# Slave_V1.net
KiCad netlist of a schematic drawn in Altium Designer
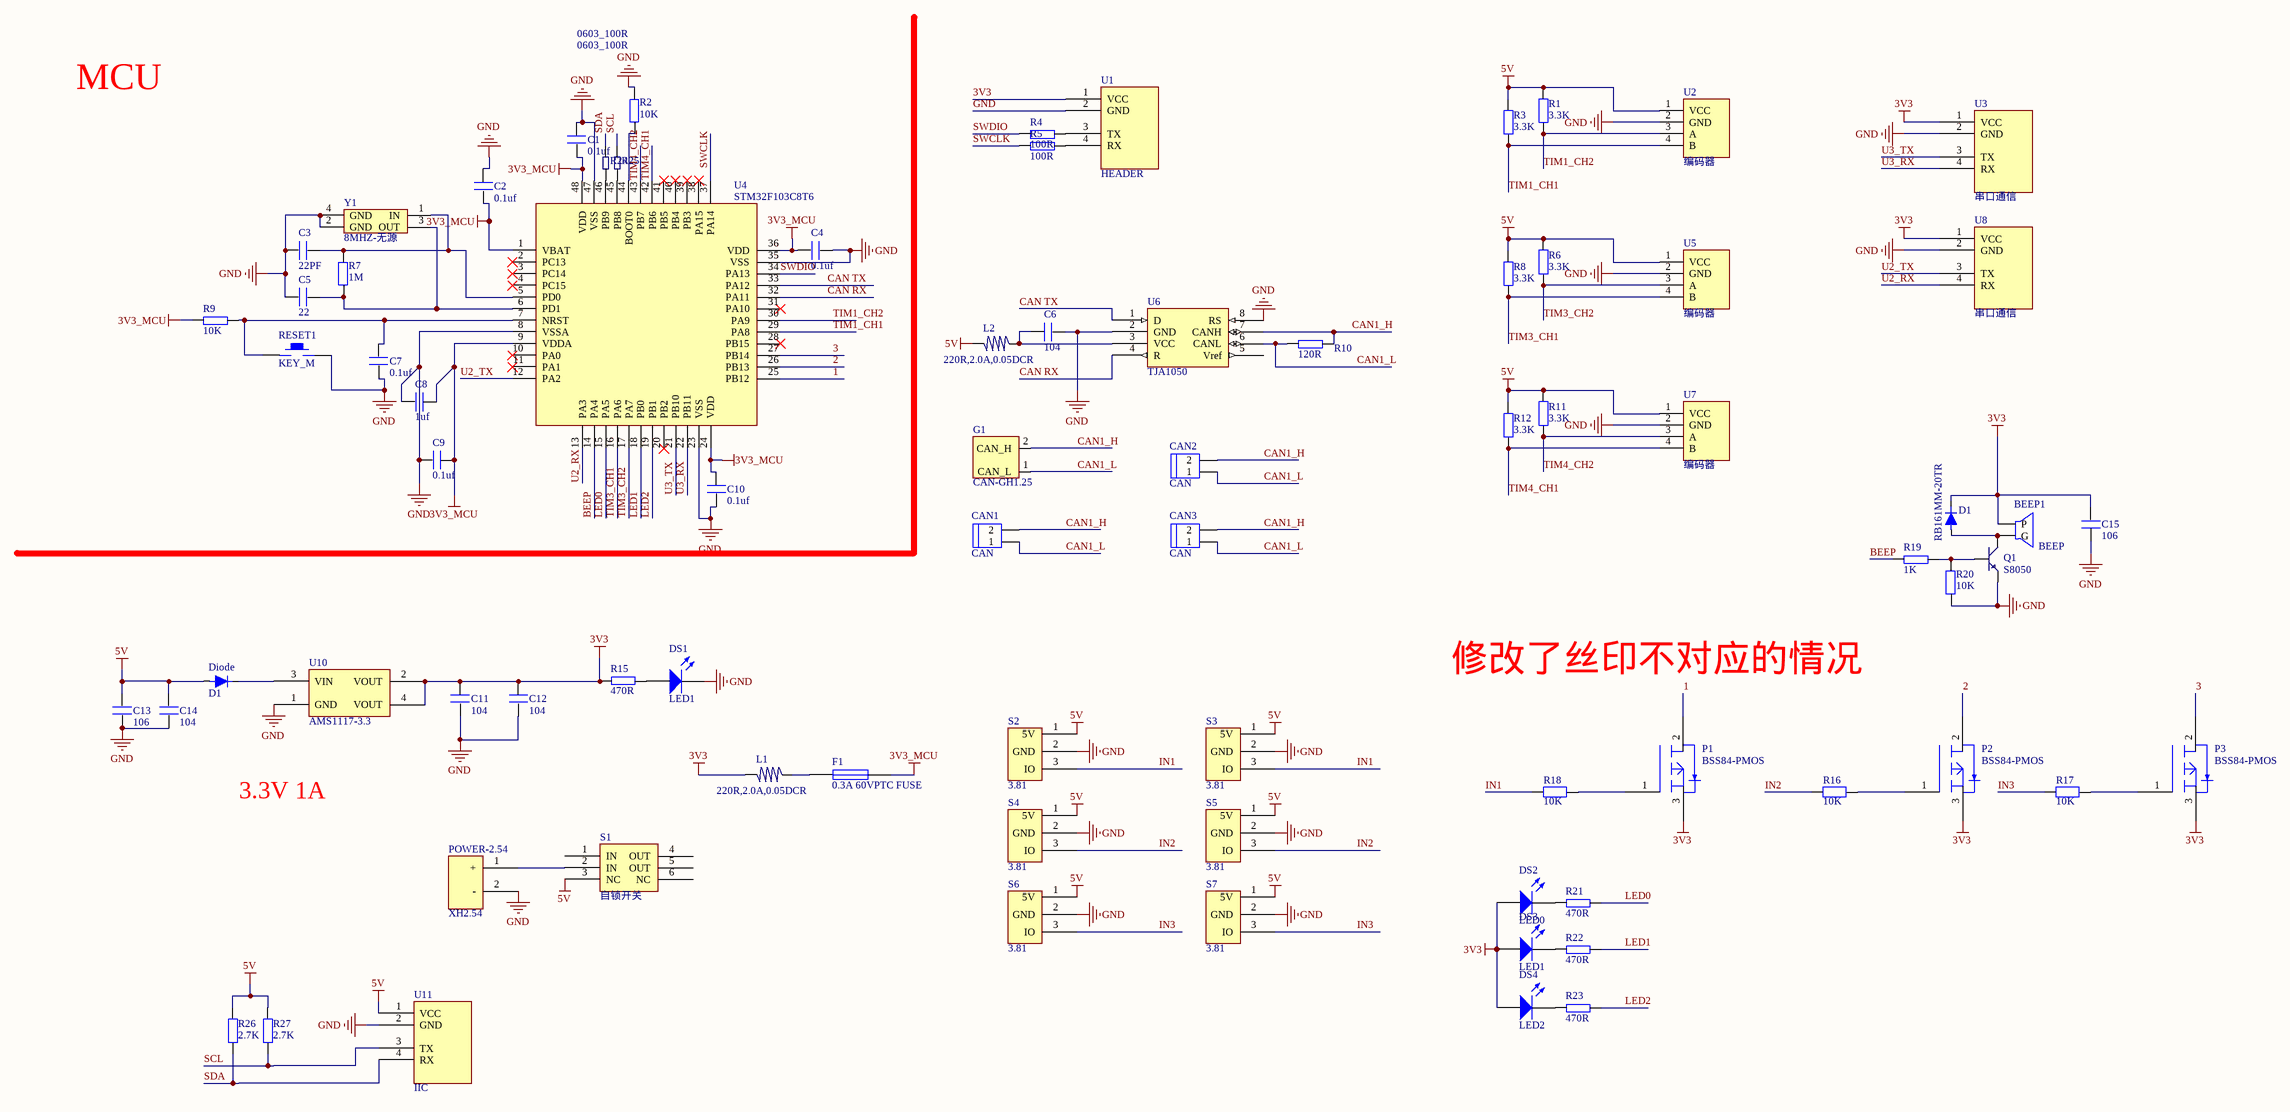
[diagram p0: Slave_V1.SchDoc]

(export (version "E")
  (design (tool "Eeschema 10.0.6"))
  (components
    (comp (ref "BEEP1")
      (value "BEEP")
      (footprint "BELL-5")
      (libsource (lib "Explorer STM32F407封装库") (part "BEEP"))
    )
    (comp (ref "C1") (value "0.1uf") (footprint "0603P") (libsource (lib "Explorer STM32F407封装库") (part "C")))
    (comp (ref "C2") (value "0.1uf") (footprint "0603P") (libsource (lib "Explorer STM32F407封装库") (part "C")))
    (comp (ref "C3") (value "22PF") (footprint "0603P") (libsource (lib "Explorer STM32F407封装库") (part "C")))
    (comp (ref "C4") (value "0.1uf") (footprint "0603P") (libsource (lib "Explorer STM32F407封装库") (part "C")))
    (comp (ref "C5") (value "22") (footprint "0603P") (libsource (lib "Explorer STM32F407封装库") (part "C")))
    (comp (ref "C6") (value "104") (footprint "0603P") (libsource (lib "Explorer STM32F407封装库") (part "C")))
    (comp (ref "C7") (value "0.1uf") (footprint "0603P") (libsource (lib "Explorer STM32F407封装库") (part "C")))
    (comp (ref "C8") (value "1uf") (footprint "0603P") (libsource (lib "Explorer STM32F407封装库") (part "C")))
    (comp (ref "C9") (value "0.1uf") (footprint "0603P") (libsource (lib "Explorer STM32F407封装库") (part "C")))
    (comp (ref "C10")
      (value "0.1uf")
      (footprint "0603P")
      (libsource (lib "Explorer STM32F407封装库") (part "C"))
    )
    (comp (ref "C11")
      (value "104")
      (footprint "0603P")
      (libsource (lib "Explorer STM32F407封装库_SCH") (part "C"))
    )
    (comp (ref "C12")
      (value "104")
      (footprint "0603P")
      (libsource (lib "Explorer STM32F407封装库_SCH") (part "C"))
    )
    (comp (ref "C13")
      (value "106")
      (footprint "0603P")
      (libsource (lib "Explorer STM32F407封装库_SCH") (part "C"))
    )
    (comp (ref "C14")
      (value "104")
      (footprint "0603P")
      (libsource (lib "Explorer STM32F407封装库_SCH") (part "C"))
    )
    (comp (ref "C15") (value "106") (footprint "0603C") (libsource (lib "Explorer STM32F407封装库") (part "C")))
    (comp (ref "CAN1")
      (value "CAN")
      (footprint "HEAD2L-0.8")
      (libsource (lib "Explorer STM32F407封装库") (part "HEAD2"))
    )
    (comp (ref "CAN2")
      (value "CAN")
      (footprint "XH2.54-2")
      (libsource (lib "Explorer STM32F407封装库") (part "HEAD2"))
    )
    (comp (ref "CAN3")
      (value "CAN")
      (footprint "XH2.54-2")
      (libsource (lib "Explorer STM32F407封装库") (part "HEAD2"))
    )
    (comp (ref "D1")
      (value "RB161MM-20TR")
      (footprint "LC-SOD-123F")
      (libsource (lib "主控V2.0弱电") (part "肖特基"))
    )
    (comp (ref "Diode") (value "D1") (footprint "LC-SOD-123F") (libsource (lib "SCHlib") (part "肖特基")))
    (comp (ref "DS1")
      (value "LED1")
      (footprint "0603_LED")
      (description "Typical RED, GREEN, YELLOW, AMBER GaAs LED")
      (fields (field (name "PUBLISHER") "Altium Limited"))
      (libsource (lib "Explorer STM32F407封装库") (part "LED2"))
    )
    (comp (ref "DS2")
      (value "LED0")
      (footprint "0603_LED")
      (description "Typical RED, GREEN, YELLOW, AMBER GaAs LED")
      (fields (field (name "PUBLISHER") "Altium Limited"))
      (libsource (lib "Explorer STM32F407封装库") (part "LED2"))
    )
    (comp (ref "DS3")
      (value "LED1")
      (footprint "0603_LED")
      (description "Typical RED, GREEN, YELLOW, AMBER GaAs LED")
      (fields (field (name "PUBLISHER") "Altium Limited"))
      (libsource (lib "Explorer STM32F407封装库") (part "LED2"))
    )
    (comp (ref "DS4")
      (value "LED2")
      (footprint "0603_LED")
      (description "Typical RED, GREEN, YELLOW, AMBER GaAs LED")
      (fields (field (name "PUBLISHER") "Altium Limited"))
      (libsource (lib "Explorer STM32F407封装库") (part "LED2"))
    )
    (comp (ref "F1")
      (value "0.3A 60VPTC FUSE")
      (footprint "LC-1812_R")
      (description "Fuse")
      (fields (field (name "PUBLISHER") "Altium Limited"))
      (libsource (lib "羽毛球团队") (part "Fuse 1_2"))
    )
    (comp (ref "G1")
      (value "CAN-GH1.25")
      (footprint "GH1.25_1*2_lishi")
      (libsource (lib "SCHlib") (part "GH1.25-CAN"))
    )
    (comp (ref "L1")
      (value "220R,2.0A,0.05DCR")
      (footprint "L_0603")
      (libsource (lib "Explorer STM32F407封装库") (part "L"))
    )
    (comp (ref "L2")
      (value "220R,2.0A,0.05DCR")
      (footprint "0603P")
      (libsource (lib "Explorer STM32F407封装库") (part "L"))
    )
    (comp (ref "P1")
      (value "BSS84-PMOS")
      (footprint "LC-SOT-23(SOT-23-3)")
      (libsource (lib "SCHlib") (part "BSS84-PMOS"))
    )
    (comp (ref "P2")
      (value "BSS84-PMOS")
      (footprint "LC-SOT-23(SOT-23-3)")
      (libsource (lib "SCHlib") (part "BSS84-PMOS"))
    )
    (comp (ref "P3")
      (value "BSS84-PMOS")
      (footprint "LC-SOT-23(SOT-23-3)")
      (libsource (lib "SCHlib") (part "BSS84-PMOS"))
    )
    (comp (ref "POWER-2.54")
      (value "XH2.54")
      (footprint "XH2.54-2")
      (libsource (lib "SCHlib") (part "XH2.54-2"))
    )
    (comp (ref "Q1")
      (value "S8050")
      (footprint "SOT-23R")
      (description "8050/BCW846/BCW847")
      (libsource (lib "Explorer STM32F407封装库") (part "NPN"))
    )
    (comp (ref "R1")
      (value "3.3K")
      (footprint "0603P")
      (description "R-0805")
      (libsource (lib "羽毛球团队") (part "R-0805"))
    )
    (comp (ref "R2") (value "10K") (footprint "0603P") (libsource (lib "Explorer STM32F407封装库") (part "R")))
    (comp (ref "R3")
      (value "3.3K")
      (footprint "0603P")
      (description "R-0805")
      (libsource (lib "羽毛球团队") (part "R-0805"))
    )
    (comp (ref "R4") (value "100R") (footprint "0603P") (libsource (lib "Explorer STM32F407封装库") (part "R")))
    (comp (ref "R5") (value "100R") (footprint "0603P") (libsource (lib "Explorer STM32F407封装库") (part "R")))
    (comp (ref "R6")
      (value "3.3K")
      (footprint "0603P")
      (description "R-0805")
      (libsource (lib "羽毛球团队") (part "R-0805"))
    )
    (comp (ref "R7") (value "1M") (footprint "0603P") (libsource (lib "Explorer STM32F407封装库") (part "R")))
    (comp (ref "R8")
      (value "3.3K")
      (footprint "0603P")
      (description "R-0805")
      (libsource (lib "羽毛球团队") (part "R-0805"))
    )
    (comp (ref "R9") (value "10K") (footprint "0603P") (libsource (lib "Explorer STM32F407封装库") (part "R")))
    (comp (ref "R10") (value "120R") (footprint "0603P") (libsource (lib "Explorer STM32F407封装库") (part "R")))
    (comp (ref "R11")
      (value "3.3K")
      (footprint "0603P")
      (description "R-0805")
      (libsource (lib "羽毛球团队") (part "R-0805"))
    )
    (comp (ref "R12")
      (value "3.3K")
      (footprint "0603P")
      (description "R-0805")
      (libsource (lib "羽毛球团队") (part "R-0805"))
    )
    (comp (ref "R15")
      (value "470R")
      (footprint "0603P")
      (libsource (lib "Explorer STM32F407封装库_SCH") (part "R"))
    )
    (comp (ref "R16")
      (value "10K")
      (footprint "0603P")
      (description "R-0805")
      (libsource (lib "") (part "R-0805_1"))
    )
    (comp (ref "R17")
      (value "10K")
      (footprint "0603P")
      (description "R-0805")
      (libsource (lib "") (part "R-0805_1"))
    )
    (comp (ref "R18")
      (value "10K")
      (footprint "0603P")
      (description "R-0805")
      (libsource (lib "") (part "R-0805_1"))
    )
    (comp (ref "R19") (value "1K") (footprint "0603R") (libsource (lib "Explorer STM32F407封装库") (part "R")))
    (comp (ref "R20") (value "10K") (footprint "0603R") (libsource (lib "Explorer STM32F407封装库") (part "R")))
    (comp (ref "R21") (value "470R") (footprint "0603R") (libsource (lib "Explorer STM32F407封装库") (part "R")))
    (comp (ref "R22") (value "470R") (footprint "0603R") (libsource (lib "Explorer STM32F407封装库") (part "R")))
    (comp (ref "R23") (value "470R") (footprint "0603R") (libsource (lib "Explorer STM32F407封装库") (part "R")))
    (comp (ref "R24") (value "0603_100R") (footprint "0603R") (libsource (lib "Schlib1") (part "RES")))
    (comp (ref "R25") (value "0603_100R") (footprint "0603R") (libsource (lib "Schlib1") (part "RES")))
    (comp (ref "R26")
      (value "2.7K")
      (footprint "0603R")
      (description "R-0805")
      (libsource (lib "") (part "R-0805_2"))
    )
    (comp (ref "R27")
      (value "2.7K")
      (footprint "0603R")
      (description "R-0805")
      (libsource (lib "") (part "R-0805_2"))
    )
    (comp (ref "RESET1")
      (value "KEY_M")
      (footprint "KEY_M")
      (libsource (lib "Explorer STM32F407封装库_SCH") (part "KEY_M"))
    )
    (comp (ref "S1") (value "自锁开关") (footprint "自锁开关5.8*5.8") (libsource (lib "SCHlib") (part "Switch_5.8")))
    (comp (ref "S2") (value "3.81") (footprint "KF2EDG-3.81-3P-弯针") (libsource (lib "SCHlib") (part "槽型开关")))
    (comp (ref "S3") (value "3.81") (footprint "KF2EDG-3.81-3P-弯针") (libsource (lib "SCHlib") (part "槽型开关")))
    (comp (ref "S4") (value "3.81") (footprint "KF2EDG-3.81-3P-弯针") (libsource (lib "SCHlib") (part "槽型开关")))
    (comp (ref "S5") (value "3.81") (footprint "KF2EDG-3.81-3P-弯针") (libsource (lib "SCHlib") (part "槽型开关")))
    (comp (ref "S6") (value "3.81") (footprint "KF2EDG-3.81-3P-弯针") (libsource (lib "SCHlib") (part "槽型开关")))
    (comp (ref "S7") (value "3.81") (footprint "KF2EDG-3.81-3P-弯针") (libsource (lib "SCHlib") (part "槽型开关")))
    (comp (ref "U1") (value "HEADER") (footprint "XH2.54-4") (libsource (lib "羽毛球团队") (part "XH2.54插座-4P")))
    (comp (ref "U2") (value "编码器") (footprint "XH2.54-4") (libsource (lib "SCHlib") (part "编码器4P")))
    (comp (ref "U3") (value "串口通信") (footprint "XH2.54-4") (libsource (lib "羽毛球团队") (part "XH2.54插座-4P")))
    (comp (ref "U4")
      (value "STM32F103C8T6")
      (footprint "LQFP-48_7x7x05P")
      (libsource (lib "RoboFly") (part "STM32F103C8T6"))
    )
    (comp (ref "U5") (value "编码器") (footprint "XH2.54-4") (libsource (lib "SCHlib") (part "编码器4P")))
    (comp (ref "U6")
      (value "TJA1050")
      (footprint "SOP8")
      (libsource (lib "Explorer STM32F407封装库") (part "SN65HVD230D"))
    )
    (comp (ref "U7") (value "编码器") (footprint "XH2.54-4") (libsource (lib "SCHlib") (part "编码器4P")))
    (comp (ref "U8") (value "串口通信") (footprint "XH2.54-4") (libsource (lib "羽毛球团队") (part "XH2.54插座-4P")))
    (comp (ref "U10") (value "AMS1117-3.3") (footprint "SOT223") (libsource (lib "74hc595") (part "AMS1117")))
    (comp (ref "U11") (value "IIC") (footprint "XH2.54-4") (libsource (lib "羽毛球团队") (part "XH2.54插座-4P")))
    (comp (ref "Y1")
      (value "8MHZ-无源")
      (footprint "XTAL3225   无源")
      (libsource (lib "SCHlib") (part "XTAL-3225"))
    )
  )
  (nets
    (net (code "1") (name "/1") (class "Default")
      (node (ref "P1") (pin "2") (pinfunction "D_2") (pintype "passive"))
      (node (ref "U4") (pin "25") (pinfunction "PB12_25") (pintype "passive"))
    )
    (net (code "2") (name "/2") (class "Default")
      (node (ref "P2") (pin "2") (pinfunction "D_2") (pintype "passive"))
      (node (ref "U4") (pin "26") (pinfunction "PB13_26") (pintype "passive"))
    )
    (net (code "3") (name "/3") (class "Default")
      (node (ref "P3") (pin "2") (pinfunction "D_2") (pintype "passive"))
      (node (ref "U4") (pin "27") (pinfunction "PB14_27") (pintype "passive"))
    )
    (net (code "4") (name "/BEEP") (class "Default")
      (node (ref "R19") (pin "1") (pintype "passive"))
      (node (ref "U4") (pin "14") (pinfunction "PA4_14") (pintype "passive"))
    )
    (net (code "5") (name "/CAN RX") (class "Default")
      (node (ref "U4") (pin "32") (pinfunction "PA11_32") (pintype "passive"))
      (node (ref "U6") (pin "4") (pinfunction "R_4") (pintype "output"))
    )
    (net (code "6") (name "/CAN TX") (class "Default")
      (node (ref "U4") (pin "33") (pinfunction "PA12_33") (pintype "passive"))
      (node (ref "U6") (pin "1") (pinfunction "D_1") (pintype "input"))
    )
    (net (code "7") (name "/CAN1_H") (class "Default")
      (node (ref "CAN1") (pin "2") (pinfunction "2_2") (pintype "passive"))
      (node (ref "CAN2") (pin "2") (pinfunction "2_2") (pintype "passive"))
      (node (ref "CAN3") (pin "2") (pinfunction "2_2") (pintype "passive"))
      (node (ref "G1") (pin "2") (pinfunction "CAN_H_2") (pintype "passive"))
      (node (ref "R10") (pin "2") (pintype "passive"))
      (node (ref "U6") (pin "7") (pinfunction "CANH_7") (pintype "bidirectional"))
    )
    (net (code "8") (name "/CAN1_L") (class "Default")
      (node (ref "CAN1") (pin "1") (pinfunction "1_1") (pintype "passive"))
      (node (ref "CAN2") (pin "1") (pinfunction "1_1") (pintype "passive"))
      (node (ref "CAN3") (pin "1") (pinfunction "1_1") (pintype "passive"))
      (node (ref "G1") (pin "1") (pinfunction "CAN_L_1") (pintype "passive"))
      (node (ref "R10") (pin "1") (pintype "passive"))
      (node (ref "U6") (pin "6") (pinfunction "CANL_6") (pintype "bidirectional"))
    )
    (net (code "9") (name "/IN1") (class "Default")
      (node (ref "R18") (pin "1") (pinfunction "1_1") (pintype "passive"))
      (node (ref "S2") (pin "3") (pinfunction "IO_3") (pintype "passive"))
      (node (ref "S3") (pin "3") (pinfunction "IO_3") (pintype "passive"))
    )
    (net (code "10") (name "/IN2") (class "Default")
      (node (ref "R16") (pin "1") (pinfunction "1_1") (pintype "passive"))
      (node (ref "S4") (pin "3") (pinfunction "IO_3") (pintype "passive"))
      (node (ref "S5") (pin "3") (pinfunction "IO_3") (pintype "passive"))
    )
    (net (code "11") (name "/IN3") (class "Default")
      (node (ref "R17") (pin "1") (pinfunction "1_1") (pintype "passive"))
      (node (ref "S6") (pin "3") (pinfunction "IO_3") (pintype "passive"))
      (node (ref "S7") (pin "3") (pinfunction "IO_3") (pintype "passive"))
    )
    (net (code "12") (name "/LED0") (class "Default")
      (node (ref "R21") (pin "2") (pintype "passive"))
      (node (ref "U4") (pin "15") (pinfunction "PA5_15") (pintype "passive"))
    )
    (net (code "13") (name "/LED1") (class "Default")
      (node (ref "R22") (pin "2") (pintype "passive"))
      (node (ref "U4") (pin "18") (pinfunction "PB0_18") (pintype "passive"))
    )
    (net (code "14") (name "/LED2") (class "Default")
      (node (ref "R23") (pin "2") (pintype "passive"))
      (node (ref "U4") (pin "19") (pinfunction "PB1_19") (pintype "passive"))
    )
    (net (code "15") (name "/SCL") (class "Default")
      (node (ref "R25") (pin "2") (pinfunction "2_2") (pintype "passive"))
      (node (ref "R27") (pin "1") (pinfunction "1_1") (pintype "passive"))
      (node (ref "U11") (pin "3") (pinfunction "TX_3") (pintype "passive"))
    )
    (net (code "16") (name "/SDA") (class "Default")
      (node (ref "R24") (pin "2") (pinfunction "2_2") (pintype "passive"))
      (node (ref "R26") (pin "1") (pinfunction "1_1") (pintype "passive"))
      (node (ref "U11") (pin "4") (pinfunction "RX_4") (pintype "passive"))
    )
    (net (code "17") (name "/SWCLK") (class "Default")
      (node (ref "R5") (pin "1") (pintype "passive"))
      (node (ref "U4") (pin "37") (pinfunction "PA14_37") (pintype "passive"))
    )
    (net (code "18") (name "/SWDIO") (class "Default")
      (node (ref "R4") (pin "1") (pintype "passive"))
      (node (ref "U4") (pin "34") (pinfunction "PA13_34") (pintype "passive"))
    )
    (net (code "19") (name "/TIM1_CH1") (class "Default")
      (node (ref "R3") (pin "2") (pinfunction "2_2") (pintype "passive"))
      (node (ref "U2") (pin "4") (pinfunction "B_4") (pintype "passive"))
      (node (ref "U4") (pin "29") (pinfunction "PA8_29") (pintype "passive"))
    )
    (net (code "20") (name "/TIM1_CH2") (class "Default")
      (node (ref "R1") (pin "2") (pinfunction "2_2") (pintype "passive"))
      (node (ref "U2") (pin "3") (pinfunction "A_3") (pintype "passive"))
      (node (ref "U4") (pin "30") (pinfunction "PA9_30") (pintype "passive"))
    )
    (net (code "21") (name "/TIM3_CH1") (class "Default")
      (node (ref "R8") (pin "2") (pinfunction "2_2") (pintype "passive"))
      (node (ref "U4") (pin "16") (pinfunction "PA6_16") (pintype "passive"))
      (node (ref "U5") (pin "4") (pinfunction "B_4") (pintype "passive"))
    )
    (net (code "22") (name "/TIM3_CH2") (class "Default")
      (node (ref "R6") (pin "2") (pinfunction "2_2") (pintype "passive"))
      (node (ref "U4") (pin "17") (pinfunction "PA7_17") (pintype "passive"))
      (node (ref "U5") (pin "3") (pinfunction "A_3") (pintype "passive"))
    )
    (net (code "23") (name "/TIM4_CH1") (class "Default")
      (node (ref "R12") (pin "2") (pinfunction "2_2") (pintype "passive"))
      (node (ref "U4") (pin "42") (pinfunction "PB6_42") (pintype "passive"))
      (node (ref "U7") (pin "4") (pinfunction "B_4") (pintype "passive"))
    )
    (net (code "24") (name "/TIM4_CH2") (class "Default")
      (node (ref "R11") (pin "2") (pinfunction "2_2") (pintype "passive"))
      (node (ref "U4") (pin "43") (pinfunction "PB7_43") (pintype "passive"))
      (node (ref "U7") (pin "3") (pinfunction "A_3") (pintype "passive"))
    )
    (net (code "25") (name "/U2_RX") (class "Default")
      (node (ref "U4") (pin "13") (pinfunction "PA3_13") (pintype "passive"))
      (node (ref "U8") (pin "4") (pinfunction "RX_4") (pintype "passive"))
    )
    (net (code "26") (name "/U2_TX") (class "Default")
      (node (ref "U4") (pin "12") (pinfunction "PA2_12") (pintype "passive"))
      (node (ref "U8") (pin "3") (pinfunction "TX_3") (pintype "passive"))
    )
    (net (code "27") (name "/U3_RX") (class "Default")
      (node (ref "U3") (pin "4") (pinfunction "RX_4") (pintype "passive"))
      (node (ref "U4") (pin "22") (pinfunction "PB11_22") (pintype "passive"))
    )
    (net (code "28") (name "/U3_TX") (class "Default")
      (node (ref "U3") (pin "3") (pinfunction "TX_3") (pintype "passive"))
      (node (ref "U4") (pin "21") (pinfunction "PB10_21") (pintype "passive"))
    )
    (net (code "29") (name "3V3") (class "Default")
      (node (ref "BEEP1") (pin "1") (pinfunction "P_1") (pintype "passive"))
      (node (ref "C11") (pin "2") (pintype "passive"))
      (node (ref "C12") (pin "2") (pintype "passive"))
      (node (ref "C15") (pin "1") (pintype "passive"))
      (node (ref "D1") (pin "2") (pinfunction "2_2") (pintype "passive"))
      (node (ref "DS2") (pin "1") (pinfunction "A_1") (pintype "passive"))
      (node (ref "DS3") (pin "1") (pinfunction "A_1") (pintype "passive"))
      (node (ref "DS4") (pin "1") (pinfunction "A_1") (pintype "passive"))
      (node (ref "L1") (pin "2") (pintype "passive"))
      (node (ref "P1") (pin "3") (pinfunction "S_3") (pintype "passive"))
      (node (ref "P2") (pin "3") (pinfunction "S_3") (pintype "passive"))
      (node (ref "P3") (pin "3") (pinfunction "S_3") (pintype "passive"))
      (node (ref "R15") (pin "2") (pintype "passive"))
      (node (ref "U1") (pin "1") (pinfunction "VCC_1") (pintype "passive"))
      (node (ref "U10") (pin "2") (pinfunction "VOUT_2") (pintype "passive"))
      (node (ref "U10") (pin "4") (pinfunction "VOUT_4") (pintype "passive"))
      (node (ref "U3") (pin "1") (pinfunction "VCC_1") (pintype "passive"))
      (node (ref "U8") (pin "1") (pinfunction "VCC_1") (pintype "passive"))
    )
    (net (code "30") (name "3V3_MCU") (class "Default")
      (node (ref "C1") (pin "1") (pintype "passive"))
      (node (ref "C10") (pin "2") (pintype "passive"))
      (node (ref "C2") (pin "1") (pintype "passive"))
      (node (ref "C4") (pin "2") (pintype "passive"))
      (node (ref "C8") (pin "1") (pintype "passive"))
      (node (ref "C9") (pin "1") (pintype "passive"))
      (node (ref "F1") (pin "2") (pinfunction "2_2") (pintype "passive"))
      (node (ref "R9") (pin "1") (pintype "passive"))
      (node (ref "U4") (pin "1") (pinfunction "VBAT_1") (pintype "passive"))
      (node (ref "U4") (pin "24") (pinfunction "VDD_24") (pintype "passive"))
      (node (ref "U4") (pin "36") (pinfunction "VDD_36") (pintype "passive"))
      (node (ref "U4") (pin "48") (pinfunction "VDD_48") (pintype "passive"))
      (node (ref "U4") (pin "9") (pinfunction "VDDA_9") (pintype "passive"))
    )
    (net (code "31") (name "5V") (class "Default")
      (node (ref "C13") (pin "2") (pintype "passive"))
      (node (ref "C14") (pin "2") (pintype "passive"))
      (node (ref "Diode") (pin "1") (pinfunction "1_1") (pintype "passive"))
      (node (ref "L2") (pin "2") (pintype "passive"))
      (node (ref "R1") (pin "1") (pinfunction "1_1") (pintype "passive"))
      (node (ref "R11") (pin "1") (pinfunction "1_1") (pintype "passive"))
      (node (ref "R12") (pin "1") (pinfunction "1_1") (pintype "passive"))
      (node (ref "R26") (pin "2") (pinfunction "2_2") (pintype "passive"))
      (node (ref "R27") (pin "2") (pinfunction "2_2") (pintype "passive"))
      (node (ref "R3") (pin "1") (pinfunction "1_1") (pintype "passive"))
      (node (ref "R6") (pin "1") (pinfunction "1_1") (pintype "passive"))
      (node (ref "R8") (pin "1") (pinfunction "1_1") (pintype "passive"))
      (node (ref "S1") (pin "3") (pinfunction "NC_3") (pintype "passive"))
      (node (ref "S2") (pin "1") (pinfunction "5V_1") (pintype "passive"))
      (node (ref "S3") (pin "1") (pinfunction "5V_1") (pintype "passive"))
      (node (ref "S4") (pin "1") (pinfunction "5V_1") (pintype "passive"))
      (node (ref "S5") (pin "1") (pinfunction "5V_1") (pintype "passive"))
      (node (ref "S6") (pin "1") (pinfunction "5V_1") (pintype "passive"))
      (node (ref "S7") (pin "1") (pinfunction "5V_1") (pintype "passive"))
      (node (ref "U11") (pin "1") (pinfunction "VCC_1") (pintype "passive"))
      (node (ref "U2") (pin "1") (pinfunction "VCC_1") (pintype "passive"))
      (node (ref "U5") (pin "1") (pinfunction "VCC_1") (pintype "passive"))
      (node (ref "U7") (pin "1") (pinfunction "VCC_1") (pintype "passive"))
    )
    (net (code "32") (name "GND") (class "Default")
      (node (ref "C1") (pin "2") (pintype "passive"))
      (node (ref "C10") (pin "1") (pintype "passive"))
      (node (ref "C11") (pin "1") (pintype "passive"))
      (node (ref "C12") (pin "1") (pintype "passive"))
      (node (ref "C13") (pin "1") (pintype "passive"))
      (node (ref "C14") (pin "1") (pintype "passive"))
      (node (ref "C15") (pin "2") (pintype "passive"))
      (node (ref "C2") (pin "2") (pintype "passive"))
      (node (ref "C3") (pin "2") (pintype "passive"))
      (node (ref "C4") (pin "1") (pintype "passive"))
      (node (ref "C5") (pin "2") (pintype "passive"))
      (node (ref "C6") (pin "2") (pintype "passive"))
      (node (ref "C7") (pin "1") (pintype "passive"))
      (node (ref "C8") (pin "2") (pintype "passive"))
      (node (ref "C9") (pin "2") (pintype "passive"))
      (node (ref "DS1") (pin "2") (pinfunction "K_2") (pintype "passive"))
      (node (ref "POWER-2.54") (pin "2") (pinfunction "-_2") (pintype "passive"))
      (node (ref "Q1") (pin "1") (pinfunction "E_1") (pintype "passive"))
      (node (ref "R2") (pin "1") (pintype "passive"))
      (node (ref "R20") (pin "2") (pintype "passive"))
      (node (ref "RESET1") (pin "2") (pinfunction "2_2") (pintype "passive"))
      (node (ref "S2") (pin "2") (pinfunction "GND_2") (pintype "passive"))
      (node (ref "S3") (pin "2") (pinfunction "GND_2") (pintype "passive"))
      (node (ref "S4") (pin "2") (pinfunction "GND_2") (pintype "passive"))
      (node (ref "S5") (pin "2") (pinfunction "GND_2") (pintype "passive"))
      (node (ref "S6") (pin "2") (pinfunction "GND_2") (pintype "passive"))
      (node (ref "S7") (pin "2") (pinfunction "GND_2") (pintype "passive"))
      (node (ref "U1") (pin "2") (pinfunction "GND_2") (pintype "passive"))
      (node (ref "U10") (pin "1") (pinfunction "GND_1") (pintype "passive"))
      (node (ref "U11") (pin "2") (pinfunction "GND_2") (pintype "passive"))
      (node (ref "U2") (pin "2") (pinfunction "GND_2") (pintype "passive"))
      (node (ref "U3") (pin "2") (pinfunction "GND_2") (pintype "passive"))
      (node (ref "U4") (pin "23") (pinfunction "VSS_23") (pintype "passive"))
      (node (ref "U4") (pin "35") (pinfunction "VSS_35") (pintype "passive"))
      (node (ref "U4") (pin "47") (pinfunction "VSS_47") (pintype "passive"))
      (node (ref "U4") (pin "8") (pinfunction "VSSA_8") (pintype "passive"))
      (node (ref "U5") (pin "2") (pinfunction "GND_2") (pintype "passive"))
      (node (ref "U6") (pin "2") (pinfunction "GND_2") (pintype "power_in"))
      (node (ref "U6") (pin "8") (pinfunction "RS_8") (pintype "input"))
      (node (ref "U7") (pin "2") (pinfunction "GND_2") (pintype "passive"))
      (node (ref "U8") (pin "2") (pinfunction "GND_2") (pintype "passive"))
      (node (ref "Y1") (pin "2") (pinfunction "GND_2") (pintype "passive"))
      (node (ref "Y1") (pin "4") (pinfunction "GND_4") (pintype "passive"))
    )
    (net (code "33") (name "Net-(BEEP1-G)") (class "Default")
      (node (ref "BEEP1") (pin "2") (pinfunction "G_2") (pintype "passive"))
      (node (ref "D1") (pin "1") (pinfunction "1_1") (pintype "passive"))
      (node (ref "Q1") (pin "3") (pinfunction "C_3") (pintype "passive"))
    )
    (net (code "34") (name "Net-(DS1-A)") (class "Default")
      (node (ref "DS1") (pin "1") (pinfunction "A_1") (pintype "passive"))
      (node (ref "R15") (pin "1") (pintype "passive"))
    )
    (net (code "35") (name "Net-(DS2-K)") (class "Default")
      (node (ref "DS2") (pin "2") (pinfunction "K_2") (pintype "passive"))
      (node (ref "R21") (pin "1") (pintype "passive"))
    )
    (net (code "36") (name "Net-(DS3-K)") (class "Default")
      (node (ref "DS3") (pin "2") (pinfunction "K_2") (pintype "passive"))
      (node (ref "R22") (pin "1") (pintype "passive"))
    )
    (net (code "37") (name "Net-(DS4-K)") (class "Default")
      (node (ref "DS4") (pin "2") (pinfunction "K_2") (pintype "passive"))
      (node (ref "R23") (pin "1") (pintype "passive"))
    )
    (net (code "38") (name "Net-(F1-Pad1)") (class "Default")
      (node (ref "F1") (pin "1") (pinfunction "1_1") (pintype "passive"))
      (node (ref "L1") (pin "1") (pintype "passive"))
    )
    (net (code "39") (name "Net-(P1-G)") (class "Default")
      (node (ref "P1") (pin "1") (pinfunction "G_1") (pintype "passive"))
      (node (ref "R18") (pin "2") (pinfunction "2_2") (pintype "passive"))
    )
    (net (code "40") (name "Net-(P2-G)") (class "Default")
      (node (ref "P2") (pin "1") (pinfunction "G_1") (pintype "passive"))
      (node (ref "R16") (pin "2") (pinfunction "2_2") (pintype "passive"))
    )
    (net (code "41") (name "Net-(P3-G)") (class "Default")
      (node (ref "P3") (pin "1") (pinfunction "G_1") (pintype "passive"))
      (node (ref "R17") (pin "2") (pinfunction "2_2") (pintype "passive"))
    )
    (net (code "42") (name "Net-(POWER-2.54-+)") (class "Default")
      (node (ref "POWER-2.54") (pin "1") (pinfunction "+_1") (pintype "passive"))
      (node (ref "S1") (pin "2") (pinfunction "IN_2") (pintype "passive"))
    )
    (net (code "43") (name "Net-(Q1-B)") (class "Default")
      (node (ref "Q1") (pin "2") (pinfunction "B_2") (pintype "passive"))
      (node (ref "R19") (pin "2") (pintype "passive"))
      (node (ref "R20") (pin "1") (pintype "passive"))
    )
    (net (code "44") (name "Net-(U1-RX)") (class "Default")
      (node (ref "R5") (pin "2") (pintype "passive"))
      (node (ref "U1") (pin "4") (pinfunction "RX_4") (pintype "passive"))
    )
    (net (code "45") (name "Net-(U1-TX)") (class "Default")
      (node (ref "R4") (pin "2") (pintype "passive"))
      (node (ref "U1") (pin "3") (pinfunction "TX_3") (pintype "passive"))
    )
    (net (code "46") (name "Net-(U4-BOOT0)") (class "Default")
      (node (ref "R2") (pin "2") (pintype "passive"))
      (node (ref "U4") (pin "44") (pinfunction "BOOT0_44") (pintype "passive"))
    )
    (net (code "47") (name "Net-(U4-NRST)") (class "Default")
      (node (ref "C7") (pin "2") (pintype "passive"))
      (node (ref "R9") (pin "2") (pintype "passive"))
      (node (ref "RESET1") (pin "1") (pinfunction "1_1") (pintype "passive"))
      (node (ref "U4") (pin "7") (pinfunction "NRST_7") (pintype "passive"))
    )
    (net (code "48") (name "Net-(U4-PB8)") (class "Default")
      (node (ref "R25") (pin "1") (pinfunction "1_1") (pintype "passive"))
      (node (ref "U4") (pin "45") (pinfunction "PB8_45") (pintype "passive"))
    )
    (net (code "49") (name "Net-(U4-PB9)") (class "Default")
      (node (ref "R24") (pin "1") (pinfunction "1_1") (pintype "passive"))
      (node (ref "U4") (pin "46") (pinfunction "PB9_46") (pintype "passive"))
    )
    (net (code "50") (name "Net-(U4-PD0)") (class "Default")
      (node (ref "C3") (pin "1") (pintype "passive"))
      (node (ref "R7") (pin "1") (pintype "passive"))
      (node (ref "U4") (pin "5") (pinfunction "PD0_5") (pintype "passive"))
      (node (ref "Y1") (pin "1") (pinfunction "IN_1") (pintype "passive"))
    )
    (net (code "51") (name "Net-(U4-PD1)") (class "Default")
      (node (ref "C5") (pin "1") (pintype "passive"))
      (node (ref "R7") (pin "2") (pintype "passive"))
      (node (ref "U4") (pin "6") (pinfunction "PD1_6") (pintype "passive"))
      (node (ref "Y1") (pin "3") (pinfunction "OUT_3") (pintype "passive"))
    )
    (net (code "52") (name "Net-(U6-VCC)") (class "Default")
      (node (ref "C6") (pin "1") (pintype "passive"))
      (node (ref "L2") (pin "1") (pintype "passive"))
      (node (ref "U6") (pin "3") (pinfunction "VCC_3") (pintype "power_in"))
    )
    (net (code "53") (name "Net-(U10-VIN)") (class "Default")
      (node (ref "Diode") (pin "2") (pinfunction "2_2") (pintype "passive"))
      (node (ref "U10") (pin "3") (pinfunction "VIN_3") (pintype "passive"))
    )
    (net (code "54") (name "unconnected-(S1-IN-Pad1)") (class "Default")
      (node (ref "S1") (pin "1") (pinfunction "IN_1") (pintype "passive"))
    )
    (net (code "55") (name "unconnected-(S1-NC-Pad6)") (class "Default")
      (node (ref "S1") (pin "6") (pinfunction "NC_6") (pintype "passive"))
    )
    (net (code "56") (name "unconnected-(S1-OUT-Pad4)") (class "Default")
      (node (ref "S1") (pin "4") (pinfunction "OUT_4") (pintype "passive"))
    )
    (net (code "57") (name "unconnected-(S1-OUT-Pad5)") (class "Default")
      (node (ref "S1") (pin "5") (pinfunction "OUT_5") (pintype "passive"))
    )
    (net (code "58") (name "unconnected-(U4-PA0-Pad10)") (class "Default")
      (node (ref "U4") (pin "10") (pinfunction "PA0_10") (pintype "passive+no_connect"))
    )
    (net (code "59") (name "unconnected-(U4-PA1-Pad11)") (class "Default")
      (node (ref "U4") (pin "11") (pinfunction "PA1_11") (pintype "passive+no_connect"))
    )
    (net (code "60") (name "unconnected-(U4-PA10-Pad31)") (class "Default")
      (node (ref "U4") (pin "31") (pinfunction "PA10_31") (pintype "passive+no_connect"))
    )
    (net (code "61") (name "unconnected-(U4-PA15-Pad38)") (class "Default")
      (node (ref "U4") (pin "38") (pinfunction "PA15_38") (pintype "passive+no_connect"))
    )
    (net (code "62") (name "unconnected-(U4-PB2-Pad20)") (class "Default")
      (node (ref "U4") (pin "20") (pinfunction "PB2_20") (pintype "passive+no_connect"))
    )
    (net (code "63") (name "unconnected-(U4-PB3-Pad39)") (class "Default")
      (node (ref "U4") (pin "39") (pinfunction "PB3_39") (pintype "passive+no_connect"))
    )
    (net (code "64") (name "unconnected-(U4-PB4-Pad40)") (class "Default")
      (node (ref "U4") (pin "40") (pinfunction "PB4_40") (pintype "passive+no_connect"))
    )
    (net (code "65") (name "unconnected-(U4-PB5-Pad41)") (class "Default")
      (node (ref "U4") (pin "41") (pinfunction "PB5_41") (pintype "passive+no_connect"))
    )
    (net (code "66") (name "unconnected-(U4-PB15-Pad28)") (class "Default")
      (node (ref "U4") (pin "28") (pinfunction "PB15_28") (pintype "passive+no_connect"))
    )
    (net (code "67") (name "unconnected-(U4-PC13-Pad2)") (class "Default")
      (node (ref "U4") (pin "2") (pinfunction "PC13_2") (pintype "passive+no_connect"))
    )
    (net (code "68") (name "unconnected-(U4-PC14-Pad3)") (class "Default")
      (node (ref "U4") (pin "3") (pinfunction "PC14_3") (pintype "passive+no_connect"))
    )
    (net (code "69") (name "unconnected-(U4-PC15-Pad4)") (class "Default")
      (node (ref "U4") (pin "4") (pinfunction "PC15_4") (pintype "passive+no_connect"))
    )
    (net (code "70") (name "unconnected-(U6-Vref-Pad5)") (class "Default")
      (node (ref "U6") (pin "5") (pinfunction "Vref_5") (pintype "output"))
    )
  )
)
